# LED_BAO.net
KiCad netlist of a schematic drawn in Altium Designer
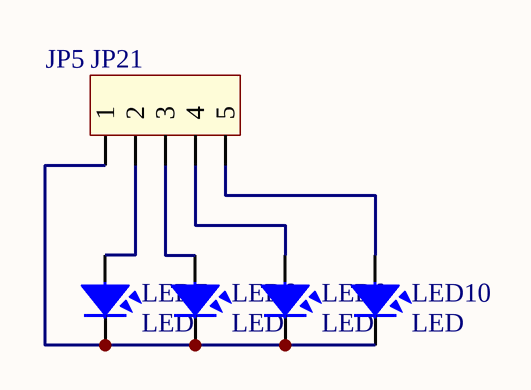
[diagram p0: LED BAO.SchDoc]

(export (version "E")
  (design (tool "Eeschema 10.0.6"))
  (components
    (comp (ref "JP21")
      (value "JP5")
      (footprint "CON5")
      (description "Connector 5")
      (libsource (lib "syhaunguyen") (part "Con5"))
    )
    (comp (ref "LED7")
      (value "LED")
      (footprint "LED-3")
      (description "Led  Vuong")
      (libsource (lib "syhaunguyen") (part "LED"))
    )
    (comp (ref "LED8")
      (value "LED")
      (footprint "LED-3")
      (description "Led  Vuong")
      (libsource (lib "syhaunguyen") (part "LED"))
    )
    (comp (ref "LED9")
      (value "LED")
      (footprint "LED-3")
      (description "Led  Vuong")
      (libsource (lib "syhaunguyen") (part "LED"))
    )
    (comp (ref "LED10")
      (value "LED")
      (footprint "LED-3")
      (description "Led  Vuong")
      (libsource (lib "syhaunguyen") (part "LED"))
    )
  )
  (nets
    (net (code "1") (name "Net-(JP21-Pad1)") (class "Default")
      (node (ref "JP21") (pin "1") (pinfunction "1_1") (pintype "passive"))
      (node (ref "LED10") (pin "2") (pinfunction "2_2") (pintype "passive"))
      (node (ref "LED7") (pin "2") (pinfunction "2_2") (pintype "passive"))
      (node (ref "LED8") (pin "2") (pinfunction "2_2") (pintype "passive"))
      (node (ref "LED9") (pin "2") (pinfunction "2_2") (pintype "passive"))
    )
    (net (code "2") (name "Net-(JP21-Pad2)") (class "Default")
      (node (ref "JP21") (pin "2") (pinfunction "2_2") (pintype "passive"))
      (node (ref "LED7") (pin "1") (pinfunction "1_1") (pintype "passive"))
    )
    (net (code "3") (name "Net-(JP21-Pad3)") (class "Default")
      (node (ref "JP21") (pin "3") (pinfunction "3_3") (pintype "passive"))
      (node (ref "LED8") (pin "1") (pinfunction "1_1") (pintype "passive"))
    )
    (net (code "4") (name "Net-(JP21-Pad4)") (class "Default")
      (node (ref "JP21") (pin "4") (pinfunction "4_4") (pintype "passive"))
      (node (ref "LED9") (pin "1") (pinfunction "1_1") (pintype "passive"))
    )
    (net (code "5") (name "Net-(JP21-Pad5)") (class "Default")
      (node (ref "JP21") (pin "5") (pinfunction "5_5") (pintype "passive"))
      (node (ref "LED10") (pin "1") (pinfunction "1_1") (pintype "passive"))
    )
  )
)
